# fpga-config.net
KiCad netlist of a schematic drawn in Altium Designer
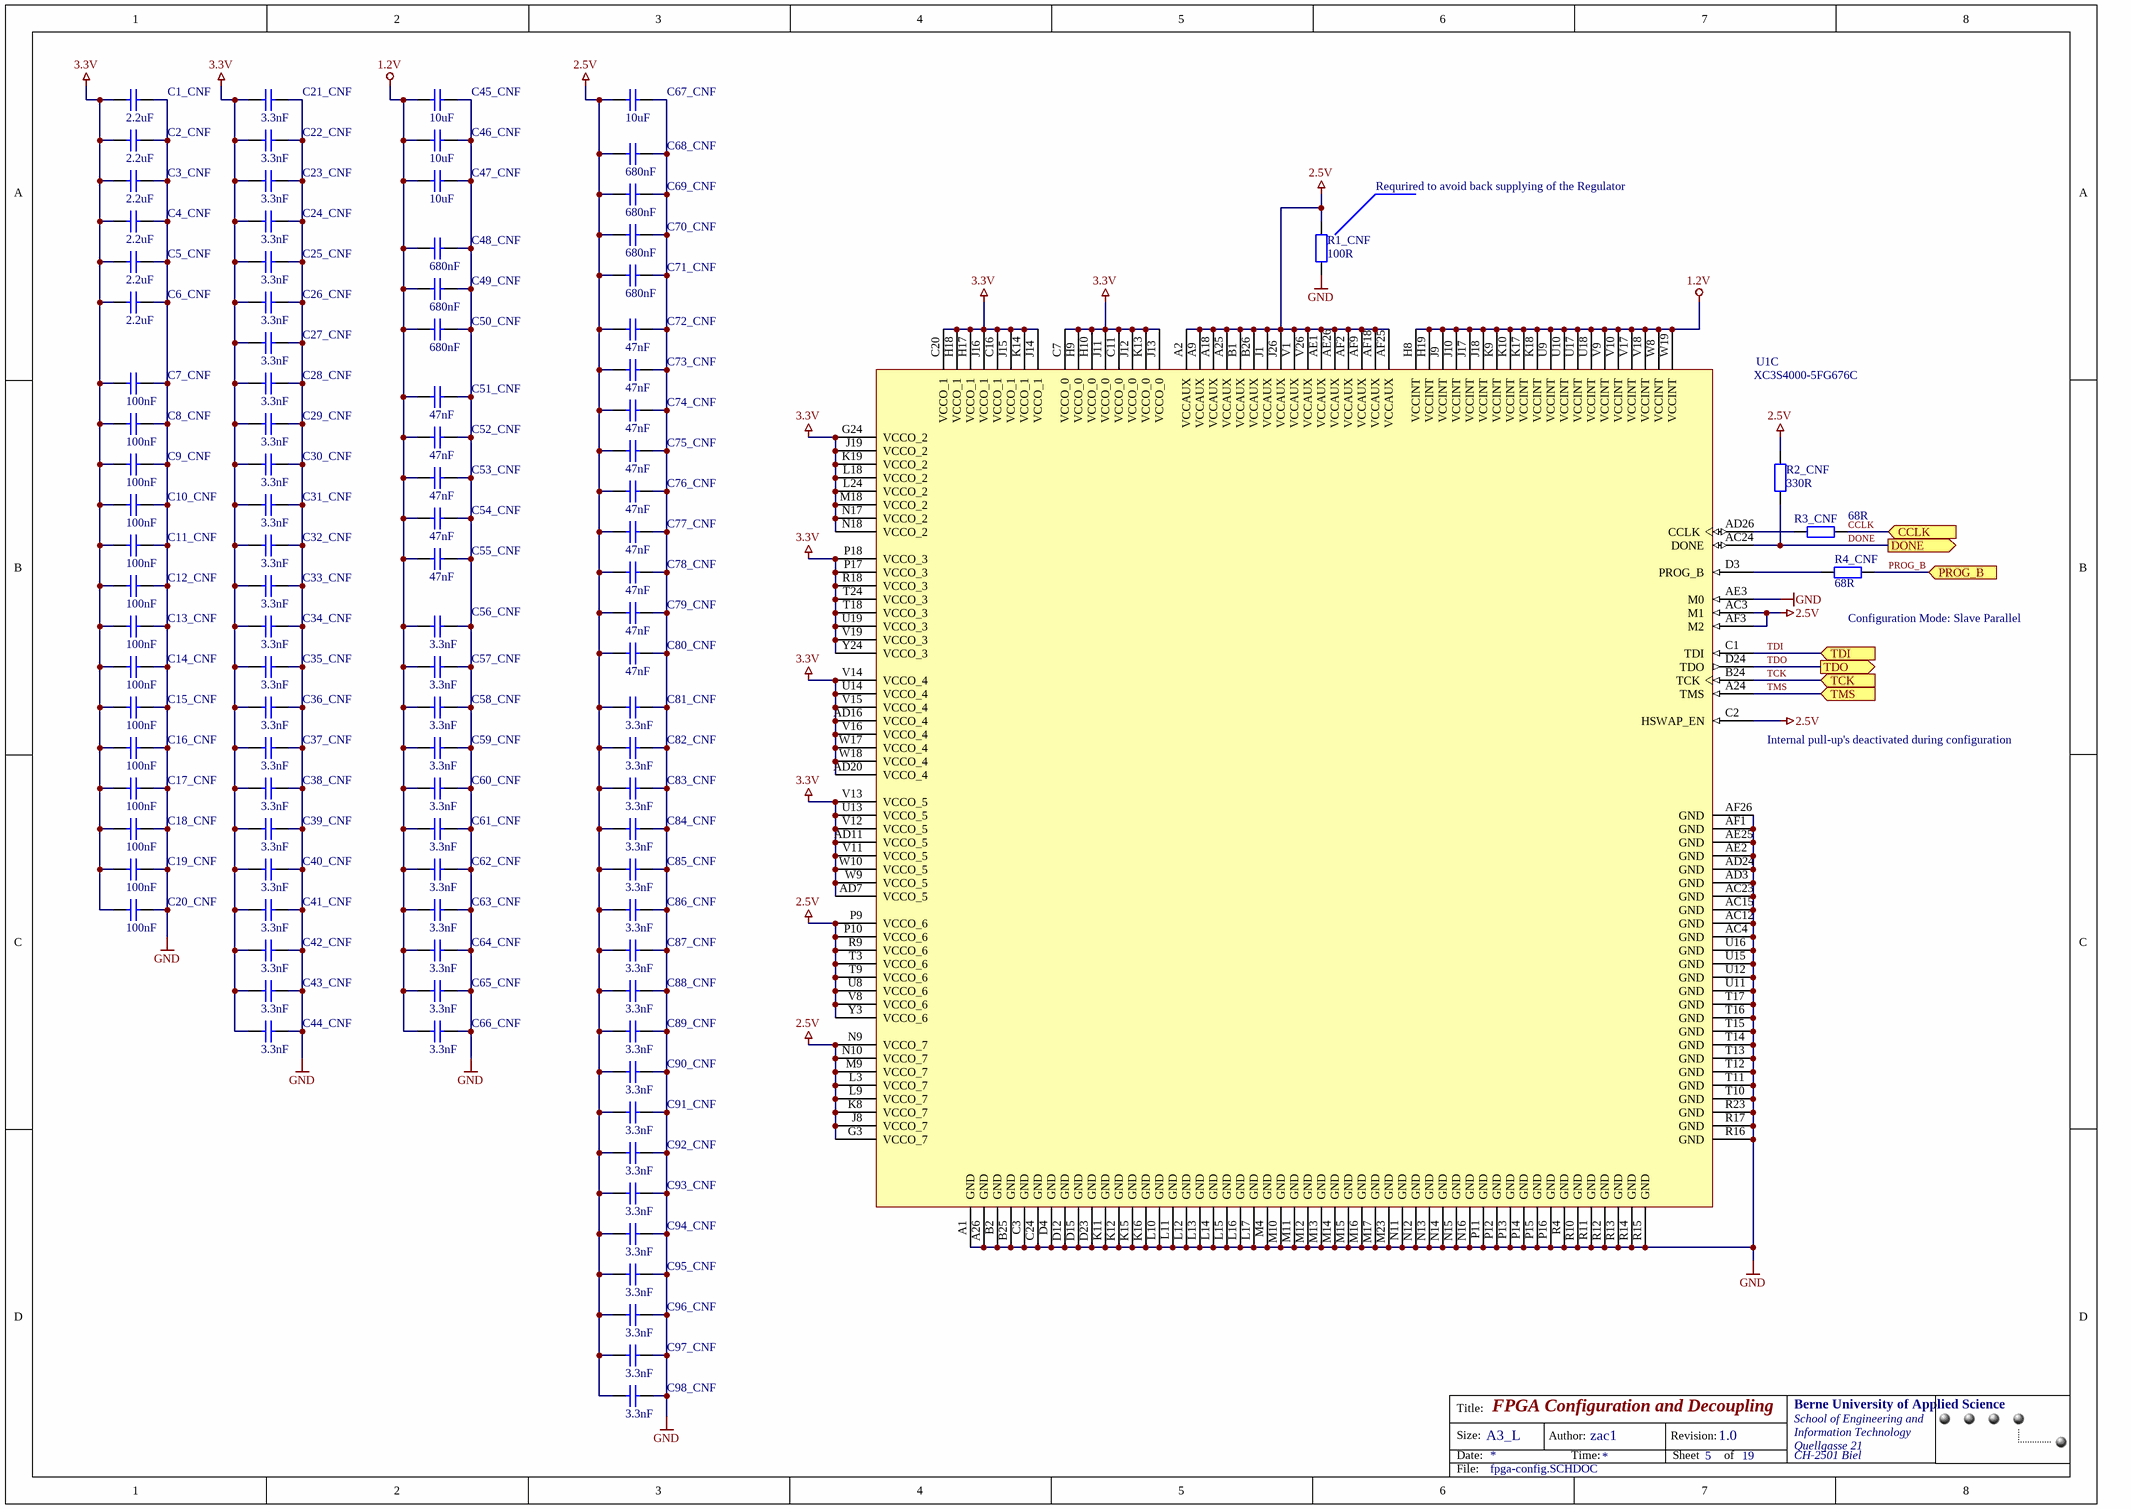
[diagram p0: fpga-config.SCHDOC]

(export (version "E")
  (design (tool "Eeschema 10.0.6"))
  (components
    (comp (ref "C1_CNF")
      (value "2.2uF")
      (footprint "0805")
      (description "Capacitor")
      (fields
        (field (name "MANUFACTURER") "Murata")
        (field (name "PART NUMBER") "GRM21BR71A225KA01L")
        (field (name "PUBLISHER") "Altium Limited")
      )
      (libsource (lib "Miscellaneous Devices") (part "Cap"))
    )
    (comp (ref "C2_CNF")
      (value "2.2uF")
      (footprint "0805")
      (description "Capacitor")
      (fields
        (field (name "MANUFACTURER") "Murata")
        (field (name "PART NUMBER") "GRM21BR71A225KA01L")
        (field (name "PUBLISHER") "Altium Limited")
      )
      (libsource (lib "Miscellaneous Devices") (part "Cap"))
    )
    (comp (ref "C3_CNF")
      (value "2.2uF")
      (footprint "0805")
      (description "Capacitor")
      (fields
        (field (name "MANUFACTURER") "Murata")
        (field (name "PART NUMBER") "GRM21BR71A225KA01L")
        (field (name "PUBLISHER") "Altium Limited")
      )
      (libsource (lib "Miscellaneous Devices") (part "Cap"))
    )
    (comp (ref "C4_CNF")
      (value "2.2uF")
      (footprint "0805")
      (description "Capacitor")
      (fields
        (field (name "MANUFACTURER") "Murata")
        (field (name "PART NUMBER") "GRM21BR71A225KA01L")
        (field (name "PUBLISHER") "Altium Limited")
      )
      (libsource (lib "Miscellaneous Devices") (part "Cap"))
    )
    (comp (ref "C5_CNF")
      (value "2.2uF")
      (footprint "0805")
      (description "Capacitor")
      (fields
        (field (name "MANUFACTURER") "Murata")
        (field (name "PART NUMBER") "GRM21BR71A225KA01L")
        (field (name "PUBLISHER") "Altium Limited")
      )
      (libsource (lib "Miscellaneous Devices") (part "Cap"))
    )
    (comp (ref "C6_CNF")
      (value "2.2uF")
      (footprint "0805")
      (description "Capacitor")
      (fields
        (field (name "MANUFACTURER") "Murata")
        (field (name "PART NUMBER") "GRM21BR71A225KA01L")
        (field (name "PUBLISHER") "Altium Limited")
      )
      (libsource (lib "Miscellaneous Devices") (part "Cap"))
    )
    (comp (ref "C7_CNF")
      (value "100nF")
      (footprint "0402")
      (description "Capacitor")
      (fields
        (field (name "MANUFACTURER") "Murata")
        (field (name "PART NUMBER") "GRM155R71C104KA88D")
        (field (name "PUBLISHER") "Altium Limited")
      )
      (libsource (lib "Miscellaneous Devices") (part "Cap"))
    )
    (comp (ref "C8_CNF")
      (value "100nF")
      (footprint "0402")
      (description "Capacitor")
      (fields
        (field (name "MANUFACTURER") "Murata")
        (field (name "PART NUMBER") "GRM155R71C104KA88D")
        (field (name "PUBLISHER") "Altium Limited")
      )
      (libsource (lib "Miscellaneous Devices") (part "Cap"))
    )
    (comp (ref "C9_CNF")
      (value "100nF")
      (footprint "0402")
      (description "Capacitor")
      (fields
        (field (name "MANUFACTURER") "Murata")
        (field (name "PART NUMBER") "GRM155R71C104KA88D")
        (field (name "PUBLISHER") "Altium Limited")
      )
      (libsource (lib "Miscellaneous Devices") (part "Cap"))
    )
    (comp (ref "C10_CNF")
      (value "100nF")
      (footprint "0402")
      (description "Capacitor")
      (fields
        (field (name "MANUFACTURER") "Murata")
        (field (name "PART NUMBER") "GRM155R71C104KA88D")
        (field (name "PUBLISHER") "Altium Limited")
      )
      (libsource (lib "Miscellaneous Devices") (part "Cap"))
    )
    (comp (ref "C11_CNF")
      (value "100nF")
      (footprint "0402")
      (description "Capacitor")
      (fields
        (field (name "MANUFACTURER") "Murata")
        (field (name "PART NUMBER") "GRM155R71C104KA88D")
        (field (name "PUBLISHER") "Altium Limited")
      )
      (libsource (lib "Miscellaneous Devices") (part "Cap"))
    )
    (comp (ref "C12_CNF")
      (value "100nF")
      (footprint "0402")
      (description "Capacitor")
      (fields
        (field (name "MANUFACTURER") "Murata")
        (field (name "PART NUMBER") "GRM155R71C104KA88D")
        (field (name "PUBLISHER") "Altium Limited")
      )
      (libsource (lib "Miscellaneous Devices") (part "Cap"))
    )
    (comp (ref "C13_CNF")
      (value "100nF")
      (footprint "0402")
      (description "Capacitor")
      (fields
        (field (name "MANUFACTURER") "Murata")
        (field (name "PART NUMBER") "GRM155R71C104KA88D")
        (field (name "PUBLISHER") "Altium Limited")
      )
      (libsource (lib "Miscellaneous Devices") (part "Cap"))
    )
    (comp (ref "C14_CNF")
      (value "100nF")
      (footprint "0402")
      (description "Capacitor")
      (fields
        (field (name "MANUFACTURER") "Murata")
        (field (name "PART NUMBER") "GRM155R71C104KA88D")
        (field (name "PUBLISHER") "Altium Limited")
      )
      (libsource (lib "Miscellaneous Devices") (part "Cap"))
    )
    (comp (ref "C15_CNF")
      (value "100nF")
      (footprint "0402")
      (description "Capacitor")
      (fields
        (field (name "MANUFACTURER") "Murata")
        (field (name "PART NUMBER") "GRM155R71C104KA88D")
        (field (name "PUBLISHER") "Altium Limited")
      )
      (libsource (lib "Miscellaneous Devices") (part "Cap"))
    )
    (comp (ref "C16_CNF")
      (value "100nF")
      (footprint "0402")
      (description "Capacitor")
      (fields
        (field (name "MANUFACTURER") "Murata")
        (field (name "PART NUMBER") "GRM155R71C104KA88D")
        (field (name "PUBLISHER") "Altium Limited")
      )
      (libsource (lib "Miscellaneous Devices") (part "Cap"))
    )
    (comp (ref "C17_CNF")
      (value "100nF")
      (footprint "0402")
      (description "Capacitor")
      (fields
        (field (name "MANUFACTURER") "Murata")
        (field (name "PART NUMBER") "GRM155R71C104KA88D")
        (field (name "PUBLISHER") "Altium Limited")
      )
      (libsource (lib "Miscellaneous Devices") (part "Cap"))
    )
    (comp (ref "C18_CNF")
      (value "100nF")
      (footprint "0402")
      (description "Capacitor")
      (fields
        (field (name "MANUFACTURER") "Murata")
        (field (name "PART NUMBER") "GRM155R71C104KA88D")
        (field (name "PUBLISHER") "Altium Limited")
      )
      (libsource (lib "Miscellaneous Devices") (part "Cap"))
    )
    (comp (ref "C19_CNF")
      (value "100nF")
      (footprint "0402")
      (description "Capacitor")
      (fields
        (field (name "MANUFACTURER") "Murata")
        (field (name "PART NUMBER") "GRM155R71C104KA88D")
        (field (name "PUBLISHER") "Altium Limited")
      )
      (libsource (lib "Miscellaneous Devices") (part "Cap"))
    )
    (comp (ref "C20_CNF")
      (value "100nF")
      (footprint "0402")
      (description "Capacitor")
      (fields
        (field (name "MANUFACTURER") "Murata")
        (field (name "PART NUMBER") "GRM155R71C104KA88D")
        (field (name "PUBLISHER") "Altium Limited")
      )
      (libsource (lib "Miscellaneous Devices") (part "Cap"))
    )
    (comp (ref "C21_CNF")
      (value "3.3nF")
      (footprint "0402")
      (description "Capacitor")
      (fields
        (field (name "MANUFACTURER") "PHYCOMP")
        (field (name "PART NUMBER") "2238 587 15629")
        (field (name "PUBLISHER") "Altium Limited")
      )
      (libsource (lib "Miscellaneous Devices") (part "Cap"))
    )
    (comp (ref "C22_CNF")
      (value "3.3nF")
      (footprint "0402")
      (description "Capacitor")
      (fields
        (field (name "MANUFACTURER") "PHYCOMP")
        (field (name "PART NUMBER") "2238 587 15629")
        (field (name "PUBLISHER") "Altium Limited")
      )
      (libsource (lib "Miscellaneous Devices") (part "Cap"))
    )
    (comp (ref "C23_CNF")
      (value "3.3nF")
      (footprint "0402")
      (description "Capacitor")
      (fields
        (field (name "MANUFACTURER") "PHYCOMP")
        (field (name "PART NUMBER") "2238 587 15629")
        (field (name "PUBLISHER") "Altium Limited")
      )
      (libsource (lib "Miscellaneous Devices") (part "Cap"))
    )
    (comp (ref "C24_CNF")
      (value "3.3nF")
      (footprint "0402")
      (description "Capacitor")
      (fields
        (field (name "MANUFACTURER") "PHYCOMP")
        (field (name "PART NUMBER") "2238 587 15629")
        (field (name "PUBLISHER") "Altium Limited")
      )
      (libsource (lib "Miscellaneous Devices") (part "Cap"))
    )
    (comp (ref "C25_CNF")
      (value "3.3nF")
      (footprint "0402")
      (description "Capacitor")
      (fields
        (field (name "MANUFACTURER") "PHYCOMP")
        (field (name "PART NUMBER") "2238 587 15629")
        (field (name "PUBLISHER") "Altium Limited")
      )
      (libsource (lib "Miscellaneous Devices") (part "Cap"))
    )
    (comp (ref "C26_CNF")
      (value "3.3nF")
      (footprint "0402")
      (description "Capacitor")
      (fields
        (field (name "MANUFACTURER") "PHYCOMP")
        (field (name "PART NUMBER") "2238 587 15629")
        (field (name "PUBLISHER") "Altium Limited")
      )
      (libsource (lib "Miscellaneous Devices") (part "Cap"))
    )
    (comp (ref "C27_CNF")
      (value "3.3nF")
      (footprint "0402")
      (description "Capacitor")
      (fields
        (field (name "MANUFACTURER") "PHYCOMP")
        (field (name "PART NUMBER") "2238 587 15629")
        (field (name "PUBLISHER") "Altium Limited")
      )
      (libsource (lib "Miscellaneous Devices") (part "Cap"))
    )
    (comp (ref "C28_CNF")
      (value "3.3nF")
      (footprint "0402")
      (description "Capacitor")
      (fields
        (field (name "MANUFACTURER") "PHYCOMP")
        (field (name "PART NUMBER") "2238 587 15629")
        (field (name "PUBLISHER") "Altium Limited")
      )
      (libsource (lib "Miscellaneous Devices") (part "Cap"))
    )
    (comp (ref "C29_CNF")
      (value "3.3nF")
      (footprint "0402")
      (description "Capacitor")
      (fields
        (field (name "MANUFACTURER") "PHYCOMP")
        (field (name "PART NUMBER") "2238 587 15629")
        (field (name "PUBLISHER") "Altium Limited")
      )
      (libsource (lib "Miscellaneous Devices") (part "Cap"))
    )
    (comp (ref "C30_CNF")
      (value "3.3nF")
      (footprint "0402")
      (description "Capacitor")
      (fields
        (field (name "MANUFACTURER") "PHYCOMP")
        (field (name "PART NUMBER") "2238 587 15629")
        (field (name "PUBLISHER") "Altium Limited")
      )
      (libsource (lib "Miscellaneous Devices") (part "Cap"))
    )
    (comp (ref "C31_CNF")
      (value "3.3nF")
      (footprint "0402")
      (description "Capacitor")
      (fields
        (field (name "MANUFACTURER") "PHYCOMP")
        (field (name "PART NUMBER") "2238 587 15629")
        (field (name "PUBLISHER") "Altium Limited")
      )
      (libsource (lib "Miscellaneous Devices") (part "Cap"))
    )
    (comp (ref "C32_CNF")
      (value "3.3nF")
      (footprint "0402")
      (description "Capacitor")
      (fields
        (field (name "MANUFACTURER") "PHYCOMP")
        (field (name "PART NUMBER") "2238 587 15629")
        (field (name "PUBLISHER") "Altium Limited")
      )
      (libsource (lib "Miscellaneous Devices") (part "Cap"))
    )
    (comp (ref "C33_CNF")
      (value "3.3nF")
      (footprint "0402")
      (description "Capacitor")
      (fields
        (field (name "MANUFACTURER") "PHYCOMP")
        (field (name "PART NUMBER") "2238 587 15629")
        (field (name "PUBLISHER") "Altium Limited")
      )
      (libsource (lib "Miscellaneous Devices") (part "Cap"))
    )
    (comp (ref "C34_CNF")
      (value "3.3nF")
      (footprint "0402")
      (description "Capacitor")
      (fields
        (field (name "MANUFACTURER") "PHYCOMP")
        (field (name "PART NUMBER") "2238 587 15629")
        (field (name "PUBLISHER") "Altium Limited")
      )
      (libsource (lib "Miscellaneous Devices") (part "Cap"))
    )
    (comp (ref "C35_CNF")
      (value "3.3nF")
      (footprint "0402")
      (description "Capacitor")
      (fields
        (field (name "MANUFACTURER") "PHYCOMP")
        (field (name "PART NUMBER") "2238 587 15629")
        (field (name "PUBLISHER") "Altium Limited")
      )
      (libsource (lib "Miscellaneous Devices") (part "Cap"))
    )
    (comp (ref "C36_CNF")
      (value "3.3nF")
      (footprint "0402")
      (description "Capacitor")
      (fields
        (field (name "MANUFACTURER") "PHYCOMP")
        (field (name "PART NUMBER") "2238 587 15629")
        (field (name "PUBLISHER") "Altium Limited")
      )
      (libsource (lib "Miscellaneous Devices") (part "Cap"))
    )
    (comp (ref "C37_CNF")
      (value "3.3nF")
      (footprint "0402")
      (description "Capacitor")
      (fields
        (field (name "MANUFACTURER") "PHYCOMP")
        (field (name "PART NUMBER") "2238 587 15629")
        (field (name "PUBLISHER") "Altium Limited")
      )
      (libsource (lib "Miscellaneous Devices") (part "Cap"))
    )
    (comp (ref "C38_CNF")
      (value "3.3nF")
      (footprint "0402")
      (description "Capacitor")
      (fields
        (field (name "MANUFACTURER") "PHYCOMP")
        (field (name "PART NUMBER") "2238 587 15629")
        (field (name "PUBLISHER") "Altium Limited")
      )
      (libsource (lib "Miscellaneous Devices") (part "Cap"))
    )
    (comp (ref "C39_CNF")
      (value "3.3nF")
      (footprint "0402")
      (description "Capacitor")
      (fields
        (field (name "MANUFACTURER") "PHYCOMP")
        (field (name "PART NUMBER") "2238 587 15629")
        (field (name "PUBLISHER") "Altium Limited")
      )
      (libsource (lib "Miscellaneous Devices") (part "Cap"))
    )
    (comp (ref "C40_CNF")
      (value "3.3nF")
      (footprint "0402")
      (description "Capacitor")
      (fields
        (field (name "MANUFACTURER") "PHYCOMP")
        (field (name "PART NUMBER") "2238 587 15629")
        (field (name "PUBLISHER") "Altium Limited")
      )
      (libsource (lib "Miscellaneous Devices") (part "Cap"))
    )
    (comp (ref "C41_CNF")
      (value "3.3nF")
      (footprint "0402")
      (description "Capacitor")
      (fields
        (field (name "MANUFACTURER") "PHYCOMP")
        (field (name "PART NUMBER") "2238 587 15629")
        (field (name "PUBLISHER") "Altium Limited")
      )
      (libsource (lib "Miscellaneous Devices") (part "Cap"))
    )
    (comp (ref "C42_CNF")
      (value "3.3nF")
      (footprint "0402")
      (description "Capacitor")
      (fields
        (field (name "MANUFACTURER") "PHYCOMP")
        (field (name "PART NUMBER") "2238 587 15629")
        (field (name "PUBLISHER") "Altium Limited")
      )
      (libsource (lib "Miscellaneous Devices") (part "Cap"))
    )
    (comp (ref "C43_CNF")
      (value "3.3nF")
      (footprint "0402")
      (description "Capacitor")
      (fields
        (field (name "MANUFACTURER") "PHYCOMP")
        (field (name "PART NUMBER") "2238 587 15629")
        (field (name "PUBLISHER") "Altium Limited")
      )
      (libsource (lib "Miscellaneous Devices") (part "Cap"))
    )
    (comp (ref "C44_CNF")
      (value "3.3nF")
      (footprint "0402")
      (description "Capacitor")
      (fields
        (field (name "MANUFACTURER") "PHYCOMP")
        (field (name "PART NUMBER") "2238 587 15629")
        (field (name "PUBLISHER") "Altium Limited")
      )
      (libsource (lib "Miscellaneous Devices") (part "Cap"))
    )
    (comp (ref "C45_CNF")
      (value "10uF")
      (footprint "1206")
      (description "Capacitor")
      (fields
        (field (name "MANUFACTURER") "Murata")
        (field (name "PART NUMBER") "GRM31CR70J106KA01L")
        (field (name "PUBLISHER") "Altium Limited")
      )
      (libsource (lib "Miscellaneous Devices") (part "Cap"))
    )
    (comp (ref "C46_CNF")
      (value "10uF")
      (footprint "1206")
      (description "Capacitor")
      (fields
        (field (name "MANUFACTURER") "Murata")
        (field (name "PART NUMBER") "GRM31CR70J106KA01L")
        (field (name "PUBLISHER") "Altium Limited")
      )
      (libsource (lib "Miscellaneous Devices") (part "Cap"))
    )
    (comp (ref "C47_CNF")
      (value "10uF")
      (footprint "1206")
      (description "Capacitor")
      (fields
        (field (name "MANUFACTURER") "Murata")
        (field (name "PART NUMBER") "GRM31CR70J106KA01L")
        (field (name "PUBLISHER") "Altium Limited")
      )
      (libsource (lib "Miscellaneous Devices") (part "Cap"))
    )
    (comp (ref "C48_CNF")
      (value "680nF")
      (footprint "0805")
      (description "Capacitor")
      (fields
        (field (name "MANUFACTURER") "PHYCOMP")
        (field (name "PART NUMBER") "2238 240 15661")
        (field (name "PUBLISHER") "Altium Limited")
      )
      (libsource (lib "Miscellaneous Devices") (part "Cap"))
    )
    (comp (ref "C49_CNF")
      (value "680nF")
      (footprint "0805")
      (description "Capacitor")
      (fields
        (field (name "MANUFACTURER") "PHYCOMP")
        (field (name "PART NUMBER") "2238 240 15661")
        (field (name "PUBLISHER") "Altium Limited")
      )
      (libsource (lib "Miscellaneous Devices") (part "Cap"))
    )
    (comp (ref "C50_CNF")
      (value "680nF")
      (footprint "0805")
      (description "Capacitor")
      (fields
        (field (name "MANUFACTURER") "PHYCOMP")
        (field (name "PART NUMBER") "2238 240 15661")
        (field (name "PUBLISHER") "Altium Limited")
      )
      (libsource (lib "Miscellaneous Devices") (part "Cap"))
    )
    (comp (ref "C51_CNF")
      (value "47nF")
      (footprint "0402")
      (description "Capacitor")
      (fields
        (field (name "MANUFACTURER") "PHYCOMP")
        (field (name "PART NUMBER") "2238 787 19845")
        (field (name "PUBLISHER") "Altium Limited")
      )
      (libsource (lib "Miscellaneous Devices") (part "Cap"))
    )
    (comp (ref "C52_CNF")
      (value "47nF")
      (footprint "0402")
      (description "Capacitor")
      (fields
        (field (name "MANUFACTURER") "PHYCOMP")
        (field (name "PART NUMBER") "2238 787 19845")
        (field (name "PUBLISHER") "Altium Limited")
      )
      (libsource (lib "Miscellaneous Devices") (part "Cap"))
    )
    (comp (ref "C53_CNF")
      (value "47nF")
      (footprint "0402")
      (description "Capacitor")
      (fields
        (field (name "MANUFACTURER") "PHYCOMP")
        (field (name "PART NUMBER") "2238 787 19845")
        (field (name "PUBLISHER") "Altium Limited")
      )
      (libsource (lib "Miscellaneous Devices") (part "Cap"))
    )
    (comp (ref "C54_CNF")
      (value "47nF")
      (footprint "0402")
      (description "Capacitor")
      (fields
        (field (name "MANUFACTURER") "PHYCOMP")
        (field (name "PART NUMBER") "2238 787 19845")
        (field (name "PUBLISHER") "Altium Limited")
      )
      (libsource (lib "Miscellaneous Devices") (part "Cap"))
    )
    (comp (ref "C55_CNF")
      (value "47nF")
      (footprint "0402")
      (description "Capacitor")
      (fields
        (field (name "MANUFACTURER") "PHYCOMP")
        (field (name "PART NUMBER") "2238 787 19845")
        (field (name "PUBLISHER") "Altium Limited")
      )
      (libsource (lib "Miscellaneous Devices") (part "Cap"))
    )
    (comp (ref "C56_CNF")
      (value "3.3nF")
      (footprint "0402")
      (description "Capacitor")
      (fields
        (field (name "MANUFACTURER") "PHYCOMP")
        (field (name "PART NUMBER") "2238 587 15629")
        (field (name "PUBLISHER") "Altium Limited")
      )
      (libsource (lib "Miscellaneous Devices") (part "Cap"))
    )
    (comp (ref "C57_CNF")
      (value "3.3nF")
      (footprint "0402")
      (description "Capacitor")
      (fields
        (field (name "MANUFACTURER") "PHYCOMP")
        (field (name "PART NUMBER") "2238 587 15629")
        (field (name "PUBLISHER") "Altium Limited")
      )
      (libsource (lib "Miscellaneous Devices") (part "Cap"))
    )
    (comp (ref "C58_CNF")
      (value "3.3nF")
      (footprint "0402")
      (description "Capacitor")
      (fields
        (field (name "MANUFACTURER") "PHYCOMP")
        (field (name "PART NUMBER") "2238 587 15629")
        (field (name "PUBLISHER") "Altium Limited")
      )
      (libsource (lib "Miscellaneous Devices") (part "Cap"))
    )
    (comp (ref "C59_CNF")
      (value "3.3nF")
      (footprint "0402")
      (description "Capacitor")
      (fields
        (field (name "MANUFACTURER") "PHYCOMP")
        (field (name "PART NUMBER") "2238 587 15629")
        (field (name "PUBLISHER") "Altium Limited")
      )
      (libsource (lib "Miscellaneous Devices") (part "Cap"))
    )
    (comp (ref "C60_CNF")
      (value "3.3nF")
      (footprint "0402")
      (description "Capacitor")
      (fields
        (field (name "MANUFACTURER") "PHYCOMP")
        (field (name "PART NUMBER") "2238 587 15629")
        (field (name "PUBLISHER") "Altium Limited")
      )
      (libsource (lib "Miscellaneous Devices") (part "Cap"))
    )
    (comp (ref "C61_CNF")
      (value "3.3nF")
      (footprint "0402")
      (description "Capacitor")
      (fields
        (field (name "MANUFACTURER") "PHYCOMP")
        (field (name "PART NUMBER") "2238 587 15629")
        (field (name "PUBLISHER") "Altium Limited")
      )
      (libsource (lib "Miscellaneous Devices") (part "Cap"))
    )
    (comp (ref "C62_CNF")
      (value "3.3nF")
      (footprint "0402")
      (description "Capacitor")
      (fields
        (field (name "MANUFACTURER") "PHYCOMP")
        (field (name "PART NUMBER") "2238 587 15629")
        (field (name "PUBLISHER") "Altium Limited")
      )
      (libsource (lib "Miscellaneous Devices") (part "Cap"))
    )
    (comp (ref "C63_CNF")
      (value "3.3nF")
      (footprint "0402")
      (description "Capacitor")
      (fields
        (field (name "MANUFACTURER") "PHYCOMP")
        (field (name "PART NUMBER") "2238 587 15629")
        (field (name "PUBLISHER") "Altium Limited")
      )
      (libsource (lib "Miscellaneous Devices") (part "Cap"))
    )
    (comp (ref "C64_CNF")
      (value "3.3nF")
      (footprint "0402")
      (description "Capacitor")
      (fields
        (field (name "MANUFACTURER") "PHYCOMP")
        (field (name "PART NUMBER") "2238 587 15629")
        (field (name "PUBLISHER") "Altium Limited")
      )
      (libsource (lib "Miscellaneous Devices") (part "Cap"))
    )
    (comp (ref "C65_CNF")
      (value "3.3nF")
      (footprint "0402")
      (description "Capacitor")
      (fields
        (field (name "MANUFACTURER") "PHYCOMP")
        (field (name "PART NUMBER") "2238 587 15629")
        (field (name "PUBLISHER") "Altium Limited")
      )
      (libsource (lib "Miscellaneous Devices") (part "Cap"))
    )
    (comp (ref "C66_CNF")
      (value "3.3nF")
      (footprint "0402")
      (description "Capacitor")
      (fields
        (field (name "MANUFACTURER") "PHYCOMP")
        (field (name "PART NUMBER") "2238 587 15629")
        (field (name "PUBLISHER") "Altium Limited")
      )
      (libsource (lib "Miscellaneous Devices") (part "Cap"))
    )
    (comp (ref "C67_CNF")
      (value "10uF")
      (footprint "1206")
      (description "Capacitor")
      (fields
        (field (name "MANUFACTURER") "Murata")
        (field (name "PART NUMBER") "GRM31CR70J106KA01L")
        (field (name "PUBLISHER") "Altium Limited")
      )
      (libsource (lib "Miscellaneous Devices") (part "Cap"))
    )
    (comp (ref "C68_CNF")
      (value "680nF")
      (footprint "0805")
      (description "Capacitor")
      (fields
        (field (name "MANUFACTURER") "PHYCOMP")
        (field (name "PART NUMBER") "2238 240 15661")
        (field (name "PUBLISHER") "Altium Limited")
      )
      (libsource (lib "Miscellaneous Devices") (part "Cap"))
    )
    (comp (ref "C69_CNF")
      (value "680nF")
      (footprint "0805")
      (description "Capacitor")
      (fields
        (field (name "MANUFACTURER") "PHYCOMP")
        (field (name "PART NUMBER") "2238 240 15661")
        (field (name "PUBLISHER") "Altium Limited")
      )
      (libsource (lib "Miscellaneous Devices") (part "Cap"))
    )
    (comp (ref "C70_CNF")
      (value "680nF")
      (footprint "0805")
      (description "Capacitor")
      (fields
        (field (name "MANUFACTURER") "PHYCOMP")
        (field (name "PART NUMBER") "2238 240 15661")
        (field (name "PUBLISHER") "Altium Limited")
      )
      (libsource (lib "Miscellaneous Devices") (part "Cap"))
    )
    (comp (ref "C71_CNF")
      (value "680nF")
      (footprint "0805")
      (description "Capacitor")
      (fields
        (field (name "MANUFACTURER") "PHYCOMP")
        (field (name "PART NUMBER") "2238 240 15661")
        (field (name "PUBLISHER") "Altium Limited")
      )
      (libsource (lib "Miscellaneous Devices") (part "Cap"))
    )
    (comp (ref "C72_CNF")
      (value "47nF")
      (footprint "0402")
      (description "Capacitor")
      (fields
        (field (name "MANUFACTURER") "PHYCOMP")
        (field (name "PART NUMBER") "2238 787 19845")
        (field (name "PUBLISHER") "Altium Limited")
      )
      (libsource (lib "Miscellaneous Devices") (part "Cap"))
    )
    (comp (ref "C73_CNF")
      (value "47nF")
      (footprint "0402")
      (description "Capacitor")
      (fields
        (field (name "MANUFACTURER") "PHYCOMP")
        (field (name "PART NUMBER") "2238 787 19845")
        (field (name "PUBLISHER") "Altium Limited")
      )
      (libsource (lib "Miscellaneous Devices") (part "Cap"))
    )
    (comp (ref "C74_CNF")
      (value "47nF")
      (footprint "0402")
      (description "Capacitor")
      (fields
        (field (name "MANUFACTURER") "PHYCOMP")
        (field (name "PART NUMBER") "2238 787 19845")
        (field (name "PUBLISHER") "Altium Limited")
      )
      (libsource (lib "Miscellaneous Devices") (part "Cap"))
    )
    (comp (ref "C75_CNF")
      (value "47nF")
      (footprint "0402")
      (description "Capacitor")
      (fields
        (field (name "MANUFACTURER") "PHYCOMP")
        (field (name "PART NUMBER") "2238 787 19845")
        (field (name "PUBLISHER") "Altium Limited")
      )
      (libsource (lib "Miscellaneous Devices") (part "Cap"))
    )
    (comp (ref "C76_CNF")
      (value "47nF")
      (footprint "0402")
      (description "Capacitor")
      (fields
        (field (name "MANUFACTURER") "PHYCOMP")
        (field (name "PART NUMBER") "2238 787 19845")
        (field (name "PUBLISHER") "Altium Limited")
      )
      (libsource (lib "Miscellaneous Devices") (part "Cap"))
    )
    (comp (ref "C77_CNF")
      (value "47nF")
      (footprint "0402")
      (description "Capacitor")
      (fields
        (field (name "MANUFACTURER") "PHYCOMP")
        (field (name "PART NUMBER") "2238 787 19845")
        (field (name "PUBLISHER") "Altium Limited")
      )
      (libsource (lib "Miscellaneous Devices") (part "Cap"))
    )
    (comp (ref "C78_CNF")
      (value "47nF")
      (footprint "0402")
      (description "Capacitor")
      (fields
        (field (name "MANUFACTURER") "PHYCOMP")
        (field (name "PART NUMBER") "2238 787 19845")
        (field (name "PUBLISHER") "Altium Limited")
      )
      (libsource (lib "Miscellaneous Devices") (part "Cap"))
    )
    (comp (ref "C79_CNF")
      (value "47nF")
      (footprint "0402")
      (description "Capacitor")
      (fields
        (field (name "MANUFACTURER") "PHYCOMP")
        (field (name "PART NUMBER") "2238 787 19845")
        (field (name "PUBLISHER") "Altium Limited")
      )
      (libsource (lib "Miscellaneous Devices") (part "Cap"))
    )
    (comp (ref "C80_CNF")
      (value "47nF")
      (footprint "0402")
      (description "Capacitor")
      (fields
        (field (name "MANUFACTURER") "PHYCOMP")
        (field (name "PART NUMBER") "2238 787 19845")
        (field (name "PUBLISHER") "Altium Limited")
      )
      (libsource (lib "Miscellaneous Devices") (part "Cap"))
    )
    (comp (ref "C81_CNF")
      (value "3.3nF")
      (footprint "0402")
      (description "Capacitor")
      (fields
        (field (name "MANUFACTURER") "PHYCOMP")
        (field (name "PART NUMBER") "2238 587 15629")
        (field (name "PUBLISHER") "Altium Limited")
      )
      (libsource (lib "Miscellaneous Devices") (part "Cap"))
    )
    (comp (ref "C82_CNF")
      (value "3.3nF")
      (footprint "0402")
      (description "Capacitor")
      (fields
        (field (name "MANUFACTURER") "PHYCOMP")
        (field (name "PART NUMBER") "2238 587 15629")
        (field (name "PUBLISHER") "Altium Limited")
      )
      (libsource (lib "Miscellaneous Devices") (part "Cap"))
    )
    (comp (ref "C83_CNF")
      (value "3.3nF")
      (footprint "0402")
      (description "Capacitor")
      (fields
        (field (name "MANUFACTURER") "PHYCOMP")
        (field (name "PART NUMBER") "2238 587 15629")
        (field (name "PUBLISHER") "Altium Limited")
      )
      (libsource (lib "Miscellaneous Devices") (part "Cap"))
    )
    (comp (ref "C84_CNF")
      (value "3.3nF")
      (footprint "0402")
      (description "Capacitor")
      (fields
        (field (name "MANUFACTURER") "PHYCOMP")
        (field (name "PART NUMBER") "2238 587 15629")
        (field (name "PUBLISHER") "Altium Limited")
      )
      (libsource (lib "Miscellaneous Devices") (part "Cap"))
    )
    (comp (ref "C85_CNF")
      (value "3.3nF")
      (footprint "0402")
      (description "Capacitor")
      (fields
        (field (name "MANUFACTURER") "PHYCOMP")
        (field (name "PART NUMBER") "2238 587 15629")
        (field (name "PUBLISHER") "Altium Limited")
      )
      (libsource (lib "Miscellaneous Devices") (part "Cap"))
    )
    (comp (ref "C86_CNF")
      (value "3.3nF")
      (footprint "0402")
      (description "Capacitor")
      (fields
        (field (name "MANUFACTURER") "PHYCOMP")
        (field (name "PART NUMBER") "2238 587 15629")
        (field (name "PUBLISHER") "Altium Limited")
      )
      (libsource (lib "Miscellaneous Devices") (part "Cap"))
    )
    (comp (ref "C87_CNF")
      (value "3.3nF")
      (footprint "0402")
      (description "Capacitor")
      (fields
        (field (name "MANUFACTURER") "PHYCOMP")
        (field (name "PART NUMBER") "2238 587 15629")
        (field (name "PUBLISHER") "Altium Limited")
      )
      (libsource (lib "Miscellaneous Devices") (part "Cap"))
    )
    (comp (ref "C88_CNF")
      (value "3.3nF")
      (footprint "0402")
      (description "Capacitor")
      (fields
        (field (name "MANUFACTURER") "PHYCOMP")
        (field (name "PART NUMBER") "2238 587 15629")
        (field (name "PUBLISHER") "Altium Limited")
      )
      (libsource (lib "Miscellaneous Devices") (part "Cap"))
    )
    (comp (ref "C89_CNF")
      (value "3.3nF")
      (footprint "0402")
      (description "Capacitor")
      (fields
        (field (name "MANUFACTURER") "PHYCOMP")
        (field (name "PART NUMBER") "2238 587 15629")
        (field (name "PUBLISHER") "Altium Limited")
      )
      (libsource (lib "Miscellaneous Devices") (part "Cap"))
    )
    (comp (ref "C90_CNF")
      (value "3.3nF")
      (footprint "0402")
      (description "Capacitor")
      (fields
        (field (name "MANUFACTURER") "PHYCOMP")
        (field (name "PART NUMBER") "2238 587 15629")
        (field (name "PUBLISHER") "Altium Limited")
      )
      (libsource (lib "Miscellaneous Devices") (part "Cap"))
    )
    (comp (ref "C91_CNF")
      (value "3.3nF")
      (footprint "0402")
      (description "Capacitor")
      (fields
        (field (name "MANUFACTURER") "PHYCOMP")
        (field (name "PART NUMBER") "2238 587 15629")
        (field (name "PUBLISHER") "Altium Limited")
      )
      (libsource (lib "Miscellaneous Devices") (part "Cap"))
    )
    (comp (ref "C92_CNF")
      (value "3.3nF")
      (footprint "0402")
      (description "Capacitor")
      (fields
        (field (name "MANUFACTURER") "PHYCOMP")
        (field (name "PART NUMBER") "2238 587 15629")
        (field (name "PUBLISHER") "Altium Limited")
      )
      (libsource (lib "Miscellaneous Devices") (part "Cap"))
    )
    (comp (ref "C93_CNF")
      (value "3.3nF")
      (footprint "0402")
      (description "Capacitor")
      (fields
        (field (name "MANUFACTURER") "PHYCOMP")
        (field (name "PART NUMBER") "2238 587 15629")
        (field (name "PUBLISHER") "Altium Limited")
      )
      (libsource (lib "Miscellaneous Devices") (part "Cap"))
    )
    (comp (ref "C94_CNF")
      (value "3.3nF")
      (footprint "0402")
      (description "Capacitor")
      (fields
        (field (name "MANUFACTURER") "PHYCOMP")
        (field (name "PART NUMBER") "2238 587 15629")
        (field (name "PUBLISHER") "Altium Limited")
      )
      (libsource (lib "Miscellaneous Devices") (part "Cap"))
    )
    (comp (ref "C95_CNF")
      (value "3.3nF")
      (footprint "0402")
      (description "Capacitor")
      (fields
        (field (name "MANUFACTURER") "PHYCOMP")
        (field (name "PART NUMBER") "2238 587 15629")
        (field (name "PUBLISHER") "Altium Limited")
      )
      (libsource (lib "Miscellaneous Devices") (part "Cap"))
    )
    (comp (ref "C96_CNF")
      (value "3.3nF")
      (footprint "0402")
      (description "Capacitor")
      (fields
        (field (name "MANUFACTURER") "PHYCOMP")
        (field (name "PART NUMBER") "2238 587 15629")
        (field (name "PUBLISHER") "Altium Limited")
      )
      (libsource (lib "Miscellaneous Devices") (part "Cap"))
    )
    (comp (ref "C97_CNF")
      (value "3.3nF")
      (footprint "0402")
      (description "Capacitor")
      (fields
        (field (name "MANUFACTURER") "PHYCOMP")
        (field (name "PART NUMBER") "2238 587 15629")
        (field (name "PUBLISHER") "Altium Limited")
      )
      (libsource (lib "Miscellaneous Devices") (part "Cap"))
    )
    (comp (ref "C98_CNF")
      (value "3.3nF")
      (footprint "0402")
      (description "Capacitor")
      (fields
        (field (name "MANUFACTURER") "PHYCOMP")
        (field (name "PART NUMBER") "2238 587 15629")
        (field (name "PUBLISHER") "Altium Limited")
      )
      (libsource (lib "Miscellaneous Devices") (part "Cap"))
    )
    (comp (ref "R1_CNF")
      (value "100R")
      (footprint "0402")
      (description "Resistor")
      (fields
        (field (name "MANUFACTURER") "PHYCOMP")
        (field (name "PART NUMBER") "232270671001")
        (field (name "PUBLISHER") "Altium Limited")
      )
      (libsource (lib "") (part "Res2_1"))
    )
    (comp (ref "R2_CNF")
      (value "330R")
      (footprint "0402")
      (description "Resistor")
      (fields
        (field (name "MANUFACTURER") "PHYCOMP")
        (field (name "PART NUMBER") "232270673301")
        (field (name "PUBLISHER") "Altium Limited")
      )
      (libsource (lib "") (part "Res2_1"))
    )
    (comp (ref "R3_CNF")
      (value "68R")
      (footprint "0402")
      (description "Resistor")
      (fields
        (field (name "MANUFACTURER") "PHYCOMP")
        (field (name "PART NUMBER") "232270676809")
        (field (name "PUBLISHER") "Altium Limited")
      )
      (libsource (lib "Miscellaneous Devices") (part "Res2"))
    )
    (comp (ref "R4_CNF")
      (value "68R")
      (footprint "0402")
      (description "Resistor")
      (fields
        (field (name "MANUFACTURER") "PHYCOMP")
        (field (name "PART NUMBER") "232270676809")
        (field (name "PUBLISHER") "Altium Limited")
      )
      (libsource (lib "Miscellaneous Devices") (part "Res2"))
    )
    (comp (ref "U1")
      (value "XC3S4000-5FG676C")
      (footprint "FG676")
      (description "Spartan-3 1.2V FPGA, 487 User I/Os, 676-ball FBGA, High Performance, Commercial Grade")
      (fields (field (name "MANUFACTURER") "Xilinx") (field (name "PUBLISHER") "Altium Limited"))
      (libsource (lib "gecko3-user") (part "XC3S1500-5FG676C"))
    )
  )
  (nets
    (net (code "1") (name "/CCLK") (class "Default")
      (node (ref "R3_CNF") (pin "1") (pinfunction "1_1") (pintype "passive"))
    )
    (net (code "2") (name "/DONE") (class "Default")
      (node (ref "R2_CNF") (pin "2") (pinfunction "2_2") (pintype "passive"))
      (node (ref "U1") (pin "AC24") (pinfunction "DONE_AC24") (pintype "bidirectional"))
    )
    (net (code "3") (name "/PROG_B") (class "Default")
      (node (ref "R4_CNF") (pin "1") (pinfunction "1_1") (pintype "passive"))
    )
    (net (code "4") (name "/TCK") (class "Default")
      (node (ref "U1") (pin "B24") (pinfunction "TCK_B24") (pintype "input"))
    )
    (net (code "5") (name "/TDI") (class "Default")
      (node (ref "U1") (pin "C1") (pinfunction "TDI_C1") (pintype "input"))
    )
    (net (code "6") (name "/TDO") (class "Default")
      (node (ref "U1") (pin "D24") (pinfunction "TDO_D24") (pintype "output"))
    )
    (net (code "7") (name "/TMS") (class "Default")
      (node (ref "U1") (pin "A24") (pinfunction "TMS_A24") (pintype "input"))
    )
    (net (code "8") (name "1.2V") (class "Default")
      (node (ref "C45_CNF") (pin "2") (pinfunction "2_2") (pintype "passive"))
      (node (ref "C46_CNF") (pin "2") (pinfunction "2_2") (pintype "passive"))
      (node (ref "C47_CNF") (pin "2") (pinfunction "2_2") (pintype "passive"))
      (node (ref "C48_CNF") (pin "2") (pinfunction "2_2") (pintype "passive"))
      (node (ref "C49_CNF") (pin "2") (pinfunction "2_2") (pintype "passive"))
      (node (ref "C50_CNF") (pin "2") (pinfunction "2_2") (pintype "passive"))
      (node (ref "C51_CNF") (pin "2") (pinfunction "2_2") (pintype "passive"))
      (node (ref "C52_CNF") (pin "2") (pinfunction "2_2") (pintype "passive"))
      (node (ref "C53_CNF") (pin "2") (pinfunction "2_2") (pintype "passive"))
      (node (ref "C54_CNF") (pin "2") (pinfunction "2_2") (pintype "passive"))
      (node (ref "C55_CNF") (pin "2") (pinfunction "2_2") (pintype "passive"))
      (node (ref "C56_CNF") (pin "2") (pinfunction "2_2") (pintype "passive"))
      (node (ref "C57_CNF") (pin "2") (pinfunction "2_2") (pintype "passive"))
      (node (ref "C58_CNF") (pin "2") (pinfunction "2_2") (pintype "passive"))
      (node (ref "C59_CNF") (pin "2") (pinfunction "2_2") (pintype "passive"))
      (node (ref "C60_CNF") (pin "2") (pinfunction "2_2") (pintype "passive"))
      (node (ref "C61_CNF") (pin "2") (pinfunction "2_2") (pintype "passive"))
      (node (ref "C62_CNF") (pin "2") (pinfunction "2_2") (pintype "passive"))
      (node (ref "C63_CNF") (pin "2") (pinfunction "2_2") (pintype "passive"))
      (node (ref "C64_CNF") (pin "2") (pinfunction "2_2") (pintype "passive"))
      (node (ref "C65_CNF") (pin "2") (pinfunction "2_2") (pintype "passive"))
      (node (ref "C66_CNF") (pin "2") (pinfunction "2_2") (pintype "passive"))
      (node (ref "U1") (pin "H19") (pinfunction "VCCINT_H19") (pintype "power_in"))
      (node (ref "U1") (pin "H8") (pinfunction "VCCINT_H8") (pintype "power_in"))
      (node (ref "U1") (pin "J10") (pinfunction "VCCINT_J10") (pintype "power_in"))
      (node (ref "U1") (pin "J17") (pinfunction "VCCINT_J17") (pintype "power_in"))
      (node (ref "U1") (pin "J18") (pinfunction "VCCINT_J18") (pintype "power_in"))
      (node (ref "U1") (pin "J9") (pinfunction "VCCINT_J9") (pintype "power_in"))
      (node (ref "U1") (pin "K10") (pinfunction "VCCINT_K10") (pintype "power_in"))
      (node (ref "U1") (pin "K17") (pinfunction "VCCINT_K17") (pintype "power_in"))
      (node (ref "U1") (pin "K18") (pinfunction "VCCINT_K18") (pintype "power_in"))
      (node (ref "U1") (pin "K9") (pinfunction "VCCINT_K9") (pintype "power_in"))
      (node (ref "U1") (pin "U10") (pinfunction "VCCINT_U10") (pintype "power_in"))
      (node (ref "U1") (pin "U17") (pinfunction "VCCINT_U17") (pintype "power_in"))
      (node (ref "U1") (pin "U18") (pinfunction "VCCINT_U18") (pintype "power_in"))
      (node (ref "U1") (pin "U9") (pinfunction "VCCINT_U9") (pintype "power_in"))
      (node (ref "U1") (pin "V10") (pinfunction "VCCINT_V10") (pintype "power_in"))
      (node (ref "U1") (pin "V17") (pinfunction "VCCINT_V17") (pintype "power_in"))
      (node (ref "U1") (pin "V18") (pinfunction "VCCINT_V18") (pintype "power_in"))
      (node (ref "U1") (pin "V9") (pinfunction "VCCINT_V9") (pintype "power_in"))
      (node (ref "U1") (pin "W19") (pinfunction "VCCINT_W19") (pintype "power_in"))
      (node (ref "U1") (pin "W8") (pinfunction "VCCINT_W8") (pintype "power_in"))
    )
    (net (code "9") (name "2.5V") (class "Default")
      (node (ref "C67_CNF") (pin "2") (pinfunction "2_2") (pintype "passive"))
      (node (ref "C68_CNF") (pin "2") (pinfunction "2_2") (pintype "passive"))
      (node (ref "C69_CNF") (pin "2") (pinfunction "2_2") (pintype "passive"))
      (node (ref "C70_CNF") (pin "2") (pinfunction "2_2") (pintype "passive"))
      (node (ref "C71_CNF") (pin "2") (pinfunction "2_2") (pintype "passive"))
      (node (ref "C72_CNF") (pin "2") (pinfunction "2_2") (pintype "passive"))
      (node (ref "C73_CNF") (pin "2") (pinfunction "2_2") (pintype "passive"))
      (node (ref "C74_CNF") (pin "2") (pinfunction "2_2") (pintype "passive"))
      (node (ref "C75_CNF") (pin "2") (pinfunction "2_2") (pintype "passive"))
      (node (ref "C76_CNF") (pin "2") (pinfunction "2_2") (pintype "passive"))
      (node (ref "C77_CNF") (pin "2") (pinfunction "2_2") (pintype "passive"))
      (node (ref "C78_CNF") (pin "2") (pinfunction "2_2") (pintype "passive"))
      (node (ref "C79_CNF") (pin "2") (pinfunction "2_2") (pintype "passive"))
      (node (ref "C80_CNF") (pin "2") (pinfunction "2_2") (pintype "passive"))
      (node (ref "C81_CNF") (pin "2") (pinfunction "2_2") (pintype "passive"))
      (node (ref "C82_CNF") (pin "2") (pinfunction "2_2") (pintype "passive"))
      (node (ref "C83_CNF") (pin "2") (pinfunction "2_2") (pintype "passive"))
      (node (ref "C84_CNF") (pin "2") (pinfunction "2_2") (pintype "passive"))
      (node (ref "C85_CNF") (pin "2") (pinfunction "2_2") (pintype "passive"))
      (node (ref "C86_CNF") (pin "2") (pinfunction "2_2") (pintype "passive"))
      (node (ref "C87_CNF") (pin "2") (pinfunction "2_2") (pintype "passive"))
      (node (ref "C88_CNF") (pin "2") (pinfunction "2_2") (pintype "passive"))
      (node (ref "C89_CNF") (pin "2") (pinfunction "2_2") (pintype "passive"))
      (node (ref "C90_CNF") (pin "2") (pinfunction "2_2") (pintype "passive"))
      (node (ref "C91_CNF") (pin "2") (pinfunction "2_2") (pintype "passive"))
      (node (ref "C92_CNF") (pin "2") (pinfunction "2_2") (pintype "passive"))
      (node (ref "C93_CNF") (pin "2") (pinfunction "2_2") (pintype "passive"))
      (node (ref "C94_CNF") (pin "2") (pinfunction "2_2") (pintype "passive"))
      (node (ref "C95_CNF") (pin "2") (pinfunction "2_2") (pintype "passive"))
      (node (ref "C96_CNF") (pin "2") (pinfunction "2_2") (pintype "passive"))
      (node (ref "C97_CNF") (pin "2") (pinfunction "2_2") (pintype "passive"))
      (node (ref "C98_CNF") (pin "2") (pinfunction "2_2") (pintype "passive"))
      (node (ref "R1_CNF") (pin "1") (pinfunction "1_1") (pintype "passive"))
      (node (ref "R2_CNF") (pin "1") (pinfunction "1_1") (pintype "passive"))
      (node (ref "U1") (pin "A18") (pinfunction "VCCAUX_A18") (pintype "power_in"))
      (node (ref "U1") (pin "A2") (pinfunction "VCCAUX_A2") (pintype "power_in"))
      (node (ref "U1") (pin "A25") (pinfunction "VCCAUX_A25") (pintype "power_in"))
      (node (ref "U1") (pin "A9") (pinfunction "VCCAUX_A9") (pintype "power_in"))
      (node (ref "U1") (pin "AC3") (pinfunction "M1_AC3") (pintype "input"))
      (node (ref "U1") (pin "AE1") (pinfunction "VCCAUX_AE1") (pintype "power_in"))
      (node (ref "U1") (pin "AE26") (pinfunction "VCCAUX_AE26") (pintype "power_in"))
      (node (ref "U1") (pin "AF18") (pinfunction "VCCAUX_AF18") (pintype "power_in"))
      (node (ref "U1") (pin "AF2") (pinfunction "VCCAUX_AF2") (pintype "power_in"))
      (node (ref "U1") (pin "AF25") (pinfunction "VCCAUX_AF25") (pintype "power_in"))
      (node (ref "U1") (pin "AF3") (pinfunction "M2_AF3") (pintype "input"))
      (node (ref "U1") (pin "AF9") (pinfunction "VCCAUX_AF9") (pintype "power_in"))
      (node (ref "U1") (pin "B1") (pinfunction "VCCAUX_B1") (pintype "power_in"))
      (node (ref "U1") (pin "B26") (pinfunction "VCCAUX_B26") (pintype "power_in"))
      (node (ref "U1") (pin "C2") (pinfunction "HSWAP_EN_C2") (pintype "input"))
      (node (ref "U1") (pin "G3") (pinfunction "VCCO_7_G3") (pintype "power_in"))
      (node (ref "U1") (pin "J1") (pinfunction "VCCAUX_J1") (pintype "power_in"))
      (node (ref "U1") (pin "J26") (pinfunction "VCCAUX_J26") (pintype "power_in"))
      (node (ref "U1") (pin "J8") (pinfunction "VCCO_7_J8") (pintype "power_in"))
      (node (ref "U1") (pin "K8") (pinfunction "VCCO_7_K8") (pintype "power_in"))
      (node (ref "U1") (pin "L3") (pinfunction "VCCO_7_L3") (pintype "power_in"))
      (node (ref "U1") (pin "L9") (pinfunction "VCCO_7_L9") (pintype "power_in"))
      (node (ref "U1") (pin "M9") (pinfunction "VCCO_7_M9") (pintype "power_in"))
      (node (ref "U1") (pin "N10") (pinfunction "VCCO_7_N10") (pintype "power_in"))
      (node (ref "U1") (pin "N9") (pinfunction "VCCO_7_N9") (pintype "power_in"))
      (node (ref "U1") (pin "P10") (pinfunction "VCCO_6_P10") (pintype "power_in"))
      (node (ref "U1") (pin "P9") (pinfunction "VCCO_6_P9") (pintype "power_in"))
      (node (ref "U1") (pin "R9") (pinfunction "VCCO_6_R9") (pintype "power_in"))
      (node (ref "U1") (pin "T3") (pinfunction "VCCO_6_T3") (pintype "power_in"))
      (node (ref "U1") (pin "T9") (pinfunction "VCCO_6_T9") (pintype "power_in"))
      (node (ref "U1") (pin "U8") (pinfunction "VCCO_6_U8") (pintype "power_in"))
      (node (ref "U1") (pin "V1") (pinfunction "VCCAUX_V1") (pintype "power_in"))
      (node (ref "U1") (pin "V26") (pinfunction "VCCAUX_V26") (pintype "power_in"))
      (node (ref "U1") (pin "V8") (pinfunction "VCCO_6_V8") (pintype "power_in"))
      (node (ref "U1") (pin "Y3") (pinfunction "VCCO_6_Y3") (pintype "power_in"))
    )
    (net (code "10") (name "3.3V") (class "Default")
      (node (ref "C10_CNF") (pin "2") (pinfunction "2_2") (pintype "passive"))
      (node (ref "C11_CNF") (pin "2") (pinfunction "2_2") (pintype "passive"))
      (node (ref "C12_CNF") (pin "2") (pinfunction "2_2") (pintype "passive"))
      (node (ref "C13_CNF") (pin "2") (pinfunction "2_2") (pintype "passive"))
      (node (ref "C14_CNF") (pin "2") (pinfunction "2_2") (pintype "passive"))
      (node (ref "C15_CNF") (pin "2") (pinfunction "2_2") (pintype "passive"))
      (node (ref "C16_CNF") (pin "2") (pinfunction "2_2") (pintype "passive"))
      (node (ref "C17_CNF") (pin "2") (pinfunction "2_2") (pintype "passive"))
      (node (ref "C18_CNF") (pin "2") (pinfunction "2_2") (pintype "passive"))
      (node (ref "C19_CNF") (pin "2") (pinfunction "2_2") (pintype "passive"))
      (node (ref "C1_CNF") (pin "1") (pinfunction "1_1") (pintype "passive"))
      (node (ref "C20_CNF") (pin "2") (pinfunction "2_2") (pintype "passive"))
      (node (ref "C21_CNF") (pin "2") (pinfunction "2_2") (pintype "passive"))
      (node (ref "C22_CNF") (pin "2") (pinfunction "2_2") (pintype "passive"))
      (node (ref "C23_CNF") (pin "2") (pinfunction "2_2") (pintype "passive"))
      (node (ref "C24_CNF") (pin "2") (pinfunction "2_2") (pintype "passive"))
      (node (ref "C25_CNF") (pin "2") (pinfunction "2_2") (pintype "passive"))
      (node (ref "C26_CNF") (pin "2") (pinfunction "2_2") (pintype "passive"))
      (node (ref "C27_CNF") (pin "2") (pinfunction "2_2") (pintype "passive"))
      (node (ref "C28_CNF") (pin "2") (pinfunction "2_2") (pintype "passive"))
      (node (ref "C29_CNF") (pin "2") (pinfunction "2_2") (pintype "passive"))
      (node (ref "C2_CNF") (pin "1") (pinfunction "1_1") (pintype "passive"))
      (node (ref "C30_CNF") (pin "2") (pinfunction "2_2") (pintype "passive"))
      (node (ref "C31_CNF") (pin "2") (pinfunction "2_2") (pintype "passive"))
      (node (ref "C32_CNF") (pin "2") (pinfunction "2_2") (pintype "passive"))
      (node (ref "C33_CNF") (pin "2") (pinfunction "2_2") (pintype "passive"))
      (node (ref "C34_CNF") (pin "2") (pinfunction "2_2") (pintype "passive"))
      (node (ref "C35_CNF") (pin "2") (pinfunction "2_2") (pintype "passive"))
      (node (ref "C36_CNF") (pin "2") (pinfunction "2_2") (pintype "passive"))
      (node (ref "C37_CNF") (pin "2") (pinfunction "2_2") (pintype "passive"))
      (node (ref "C38_CNF") (pin "2") (pinfunction "2_2") (pintype "passive"))
      (node (ref "C39_CNF") (pin "2") (pinfunction "2_2") (pintype "passive"))
      (node (ref "C3_CNF") (pin "1") (pinfunction "1_1") (pintype "passive"))
      (node (ref "C40_CNF") (pin "2") (pinfunction "2_2") (pintype "passive"))
      (node (ref "C41_CNF") (pin "2") (pinfunction "2_2") (pintype "passive"))
      (node (ref "C42_CNF") (pin "2") (pinfunction "2_2") (pintype "passive"))
      (node (ref "C43_CNF") (pin "2") (pinfunction "2_2") (pintype "passive"))
      (node (ref "C44_CNF") (pin "2") (pinfunction "2_2") (pintype "passive"))
      (node (ref "C4_CNF") (pin "1") (pinfunction "1_1") (pintype "passive"))
      (node (ref "C5_CNF") (pin "1") (pinfunction "1_1") (pintype "passive"))
      (node (ref "C6_CNF") (pin "1") (pinfunction "1_1") (pintype "passive"))
      (node (ref "C7_CNF") (pin "2") (pinfunction "2_2") (pintype "passive"))
      (node (ref "C8_CNF") (pin "2") (pinfunction "2_2") (pintype "passive"))
      (node (ref "C9_CNF") (pin "2") (pinfunction "2_2") (pintype "passive"))
      (node (ref "U1") (pin "AD11") (pinfunction "VCCO_5_AD11") (pintype "power_in"))
      (node (ref "U1") (pin "AD16") (pinfunction "VCCO_4_AD16") (pintype "power_in"))
      (node (ref "U1") (pin "AD20") (pinfunction "VCCO_4_AD20") (pintype "power_in"))
      (node (ref "U1") (pin "AD7") (pinfunction "VCCO_5_AD7") (pintype "power_in"))
      (node (ref "U1") (pin "C11") (pinfunction "VCCO_0_C11") (pintype "power_in"))
      (node (ref "U1") (pin "C16") (pinfunction "VCCO_1_C16") (pintype "power_in"))
      (node (ref "U1") (pin "C20") (pinfunction "VCCO_1_C20") (pintype "power_in"))
      (node (ref "U1") (pin "C7") (pinfunction "VCCO_0_C7") (pintype "power_in"))
      (node (ref "U1") (pin "G24") (pinfunction "VCCO_2_G24") (pintype "power_in"))
      (node (ref "U1") (pin "H10") (pinfunction "VCCO_0_H10") (pintype "power_in"))
      (node (ref "U1") (pin "H17") (pinfunction "VCCO_1_H17") (pintype "power_in"))
      (node (ref "U1") (pin "H18") (pinfunction "VCCO_1_H18") (pintype "power_in"))
      (node (ref "U1") (pin "H9") (pinfunction "VCCO_0_H9") (pintype "power_in"))
      (node (ref "U1") (pin "J11") (pinfunction "VCCO_0_J11") (pintype "power_in"))
      (node (ref "U1") (pin "J12") (pinfunction "VCCO_0_J12") (pintype "power_in"))
      (node (ref "U1") (pin "J13") (pinfunction "VCCO_0_J13") (pintype "power_in"))
      (node (ref "U1") (pin "J14") (pinfunction "VCCO_1_J14") (pintype "power_in"))
      (node (ref "U1") (pin "J15") (pinfunction "VCCO_1_J15") (pintype "power_in"))
      (node (ref "U1") (pin "J16") (pinfunction "VCCO_1_J16") (pintype "power_in"))
      (node (ref "U1") (pin "J19") (pinfunction "VCCO_2_J19") (pintype "power_in"))
      (node (ref "U1") (pin "K13") (pinfunction "VCCO_0_K13") (pintype "power_in"))
      (node (ref "U1") (pin "K14") (pinfunction "VCCO_1_K14") (pintype "power_in"))
      (node (ref "U1") (pin "K19") (pinfunction "VCCO_2_K19") (pintype "power_in"))
      (node (ref "U1") (pin "L18") (pinfunction "VCCO_2_L18") (pintype "power_in"))
      (node (ref "U1") (pin "L24") (pinfunction "VCCO_2_L24") (pintype "power_in"))
      (node (ref "U1") (pin "M18") (pinfunction "VCCO_2_M18") (pintype "power_in"))
      (node (ref "U1") (pin "N17") (pinfunction "VCCO_2_N17") (pintype "power_in"))
      (node (ref "U1") (pin "N18") (pinfunction "VCCO_2_N18") (pintype "power_in"))
      (node (ref "U1") (pin "P17") (pinfunction "VCCO_3_P17") (pintype "power_in"))
      (node (ref "U1") (pin "P18") (pinfunction "VCCO_3_P18") (pintype "power_in"))
      (node (ref "U1") (pin "R18") (pinfunction "VCCO_3_R18") (pintype "power_in"))
      (node (ref "U1") (pin "T18") (pinfunction "VCCO_3_T18") (pintype "power_in"))
      (node (ref "U1") (pin "T24") (pinfunction "VCCO_3_T24") (pintype "power_in"))
      (node (ref "U1") (pin "U13") (pinfunction "VCCO_5_U13") (pintype "power_in"))
      (node (ref "U1") (pin "U14") (pinfunction "VCCO_4_U14") (pintype "power_in"))
      (node (ref "U1") (pin "U19") (pinfunction "VCCO_3_U19") (pintype "power_in"))
      (node (ref "U1") (pin "V11") (pinfunction "VCCO_5_V11") (pintype "power_in"))
      (node (ref "U1") (pin "V12") (pinfunction "VCCO_5_V12") (pintype "power_in"))
      (node (ref "U1") (pin "V13") (pinfunction "VCCO_5_V13") (pintype "power_in"))
      (node (ref "U1") (pin "V14") (pinfunction "VCCO_4_V14") (pintype "power_in"))
      (node (ref "U1") (pin "V15") (pinfunction "VCCO_4_V15") (pintype "power_in"))
      (node (ref "U1") (pin "V16") (pinfunction "VCCO_4_V16") (pintype "power_in"))
      (node (ref "U1") (pin "V19") (pinfunction "VCCO_3_V19") (pintype "power_in"))
      (node (ref "U1") (pin "W10") (pinfunction "VCCO_5_W10") (pintype "power_in"))
      (node (ref "U1") (pin "W17") (pinfunction "VCCO_4_W17") (pintype "power_in"))
      (node (ref "U1") (pin "W18") (pinfunction "VCCO_4_W18") (pintype "power_in"))
      (node (ref "U1") (pin "W9") (pinfunction "VCCO_5_W9") (pintype "power_in"))
      (node (ref "U1") (pin "Y24") (pinfunction "VCCO_3_Y24") (pintype "power_in"))
    )
    (net (code "11") (name "GND") (class "Default")
      (node (ref "C10_CNF") (pin "1") (pinfunction "1_1") (pintype "passive"))
      (node (ref "C11_CNF") (pin "1") (pinfunction "1_1") (pintype "passive"))
      (node (ref "C12_CNF") (pin "1") (pinfunction "1_1") (pintype "passive"))
      (node (ref "C13_CNF") (pin "1") (pinfunction "1_1") (pintype "passive"))
      (node (ref "C14_CNF") (pin "1") (pinfunction "1_1") (pintype "passive"))
      (node (ref "C15_CNF") (pin "1") (pinfunction "1_1") (pintype "passive"))
      (node (ref "C16_CNF") (pin "1") (pinfunction "1_1") (pintype "passive"))
      (node (ref "C17_CNF") (pin "1") (pinfunction "1_1") (pintype "passive"))
      (node (ref "C18_CNF") (pin "1") (pinfunction "1_1") (pintype "passive"))
      (node (ref "C19_CNF") (pin "1") (pinfunction "1_1") (pintype "passive"))
      (node (ref "C1_CNF") (pin "2") (pinfunction "2_2") (pintype "passive"))
      (node (ref "C20_CNF") (pin "1") (pinfunction "1_1") (pintype "passive"))
      (node (ref "C21_CNF") (pin "1") (pinfunction "1_1") (pintype "passive"))
      (node (ref "C22_CNF") (pin "1") (pinfunction "1_1") (pintype "passive"))
      (node (ref "C23_CNF") (pin "1") (pinfunction "1_1") (pintype "passive"))
      (node (ref "C24_CNF") (pin "1") (pinfunction "1_1") (pintype "passive"))
      (node (ref "C25_CNF") (pin "1") (pinfunction "1_1") (pintype "passive"))
      (node (ref "C26_CNF") (pin "1") (pinfunction "1_1") (pintype "passive"))
      (node (ref "C27_CNF") (pin "1") (pinfunction "1_1") (pintype "passive"))
      (node (ref "C28_CNF") (pin "1") (pinfunction "1_1") (pintype "passive"))
      (node (ref "C29_CNF") (pin "1") (pinfunction "1_1") (pintype "passive"))
      (node (ref "C2_CNF") (pin "2") (pinfunction "2_2") (pintype "passive"))
      (node (ref "C30_CNF") (pin "1") (pinfunction "1_1") (pintype "passive"))
      (node (ref "C31_CNF") (pin "1") (pinfunction "1_1") (pintype "passive"))
      (node (ref "C32_CNF") (pin "1") (pinfunction "1_1") (pintype "passive"))
      (node (ref "C33_CNF") (pin "1") (pinfunction "1_1") (pintype "passive"))
      (node (ref "C34_CNF") (pin "1") (pinfunction "1_1") (pintype "passive"))
      (node (ref "C35_CNF") (pin "1") (pinfunction "1_1") (pintype "passive"))
      (node (ref "C36_CNF") (pin "1") (pinfunction "1_1") (pintype "passive"))
      (node (ref "C37_CNF") (pin "1") (pinfunction "1_1") (pintype "passive"))
      (node (ref "C38_CNF") (pin "1") (pinfunction "1_1") (pintype "passive"))
      (node (ref "C39_CNF") (pin "1") (pinfunction "1_1") (pintype "passive"))
      (node (ref "C3_CNF") (pin "2") (pinfunction "2_2") (pintype "passive"))
      (node (ref "C40_CNF") (pin "1") (pinfunction "1_1") (pintype "passive"))
      (node (ref "C41_CNF") (pin "1") (pinfunction "1_1") (pintype "passive"))
      (node (ref "C42_CNF") (pin "1") (pinfunction "1_1") (pintype "passive"))
      (node (ref "C43_CNF") (pin "1") (pinfunction "1_1") (pintype "passive"))
      (node (ref "C44_CNF") (pin "1") (pinfunction "1_1") (pintype "passive"))
      (node (ref "C45_CNF") (pin "1") (pinfunction "1_1") (pintype "passive"))
      (node (ref "C46_CNF") (pin "1") (pinfunction "1_1") (pintype "passive"))
      (node (ref "C47_CNF") (pin "1") (pinfunction "1_1") (pintype "passive"))
      (node (ref "C48_CNF") (pin "1") (pinfunction "1_1") (pintype "passive"))
      (node (ref "C49_CNF") (pin "1") (pinfunction "1_1") (pintype "passive"))
      (node (ref "C4_CNF") (pin "2") (pinfunction "2_2") (pintype "passive"))
      (node (ref "C50_CNF") (pin "1") (pinfunction "1_1") (pintype "passive"))
      (node (ref "C51_CNF") (pin "1") (pinfunction "1_1") (pintype "passive"))
      (node (ref "C52_CNF") (pin "1") (pinfunction "1_1") (pintype "passive"))
      (node (ref "C53_CNF") (pin "1") (pinfunction "1_1") (pintype "passive"))
      (node (ref "C54_CNF") (pin "1") (pinfunction "1_1") (pintype "passive"))
      (node (ref "C55_CNF") (pin "1") (pinfunction "1_1") (pintype "passive"))
      (node (ref "C56_CNF") (pin "1") (pinfunction "1_1") (pintype "passive"))
      (node (ref "C57_CNF") (pin "1") (pinfunction "1_1") (pintype "passive"))
      (node (ref "C58_CNF") (pin "1") (pinfunction "1_1") (pintype "passive"))
      (node (ref "C59_CNF") (pin "1") (pinfunction "1_1") (pintype "passive"))
      (node (ref "C5_CNF") (pin "2") (pinfunction "2_2") (pintype "passive"))
      (node (ref "C60_CNF") (pin "1") (pinfunction "1_1") (pintype "passive"))
      (node (ref "C61_CNF") (pin "1") (pinfunction "1_1") (pintype "passive"))
      (node (ref "C62_CNF") (pin "1") (pinfunction "1_1") (pintype "passive"))
      (node (ref "C63_CNF") (pin "1") (pinfunction "1_1") (pintype "passive"))
      (node (ref "C64_CNF") (pin "1") (pinfunction "1_1") (pintype "passive"))
      (node (ref "C65_CNF") (pin "1") (pinfunction "1_1") (pintype "passive"))
      (node (ref "C66_CNF") (pin "1") (pinfunction "1_1") (pintype "passive"))
      (node (ref "C67_CNF") (pin "1") (pinfunction "1_1") (pintype "passive"))
      (node (ref "C68_CNF") (pin "1") (pinfunction "1_1") (pintype "passive"))
      (node (ref "C69_CNF") (pin "1") (pinfunction "1_1") (pintype "passive"))
      (node (ref "C6_CNF") (pin "2") (pinfunction "2_2") (pintype "passive"))
      (node (ref "C70_CNF") (pin "1") (pinfunction "1_1") (pintype "passive"))
      (node (ref "C71_CNF") (pin "1") (pinfunction "1_1") (pintype "passive"))
      (node (ref "C72_CNF") (pin "1") (pinfunction "1_1") (pintype "passive"))
      (node (ref "C73_CNF") (pin "1") (pinfunction "1_1") (pintype "passive"))
      (node (ref "C74_CNF") (pin "1") (pinfunction "1_1") (pintype "passive"))
      (node (ref "C75_CNF") (pin "1") (pinfunction "1_1") (pintype "passive"))
      (node (ref "C76_CNF") (pin "1") (pinfunction "1_1") (pintype "passive"))
      (node (ref "C77_CNF") (pin "1") (pinfunction "1_1") (pintype "passive"))
      (node (ref "C78_CNF") (pin "1") (pinfunction "1_1") (pintype "passive"))
      (node (ref "C79_CNF") (pin "1") (pinfunction "1_1") (pintype "passive"))
      (node (ref "C7_CNF") (pin "1") (pinfunction "1_1") (pintype "passive"))
      (node (ref "C80_CNF") (pin "1") (pinfunction "1_1") (pintype "passive"))
      (node (ref "C81_CNF") (pin "1") (pinfunction "1_1") (pintype "passive"))
      (node (ref "C82_CNF") (pin "1") (pinfunction "1_1") (pintype "passive"))
      (node (ref "C83_CNF") (pin "1") (pinfunction "1_1") (pintype "passive"))
      (node (ref "C84_CNF") (pin "1") (pinfunction "1_1") (pintype "passive"))
      (node (ref "C85_CNF") (pin "1") (pinfunction "1_1") (pintype "passive"))
      (node (ref "C86_CNF") (pin "1") (pinfunction "1_1") (pintype "passive"))
      (node (ref "C87_CNF") (pin "1") (pinfunction "1_1") (pintype "passive"))
      (node (ref "C88_CNF") (pin "1") (pinfunction "1_1") (pintype "passive"))
      (node (ref "C89_CNF") (pin "1") (pinfunction "1_1") (pintype "passive"))
      (node (ref "C8_CNF") (pin "1") (pinfunction "1_1") (pintype "passive"))
      (node (ref "C90_CNF") (pin "1") (pinfunction "1_1") (pintype "passive"))
      (node (ref "C91_CNF") (pin "1") (pinfunction "1_1") (pintype "passive"))
      (node (ref "C92_CNF") (pin "1") (pinfunction "1_1") (pintype "passive"))
      (node (ref "C93_CNF") (pin "1") (pinfunction "1_1") (pintype "passive"))
      (node (ref "C94_CNF") (pin "1") (pinfunction "1_1") (pintype "passive"))
      (node (ref "C95_CNF") (pin "1") (pinfunction "1_1") (pintype "passive"))
      (node (ref "C96_CNF") (pin "1") (pinfunction "1_1") (pintype "passive"))
      (node (ref "C97_CNF") (pin "1") (pinfunction "1_1") (pintype "passive"))
      (node (ref "C98_CNF") (pin "1") (pinfunction "1_1") (pintype "passive"))
      (node (ref "C9_CNF") (pin "1") (pinfunction "1_1") (pintype "passive"))
      (node (ref "R1_CNF") (pin "2") (pinfunction "2_2") (pintype "passive"))
      (node (ref "U1") (pin "A1") (pinfunction "GND_A1") (pintype "power_in"))
      (node (ref "U1") (pin "A26") (pinfunction "GND_A26") (pintype "power_in"))
      (node (ref "U1") (pin "AC12") (pinfunction "GND_AC12") (pintype "power_in"))
      (node (ref "U1") (pin "AC15") (pinfunction "GND_AC15") (pintype "power_in"))
      (node (ref "U1") (pin "AC23") (pinfunction "GND_AC23") (pintype "power_in"))
      (node (ref "U1") (pin "AC4") (pinfunction "GND_AC4") (pintype "power_in"))
      (node (ref "U1") (pin "AD24") (pinfunction "GND_AD24") (pintype "power_in"))
      (node (ref "U1") (pin "AD3") (pinfunction "GND_AD3") (pintype "power_in"))
      (node (ref "U1") (pin "AE2") (pinfunction "GND_AE2") (pintype "power_in"))
      (node (ref "U1") (pin "AE25") (pinfunction "GND_AE25") (pintype "power_in"))
      (node (ref "U1") (pin "AE3") (pinfunction "M0_AE3") (pintype "input"))
      (node (ref "U1") (pin "AF1") (pinfunction "GND_AF1") (pintype "power_in"))
      (node (ref "U1") (pin "AF26") (pinfunction "GND_AF26") (pintype "power_in"))
      (node (ref "U1") (pin "B2") (pinfunction "GND_B2") (pintype "power_in"))
      (node (ref "U1") (pin "B25") (pinfunction "GND_B25") (pintype "power_in"))
      (node (ref "U1") (pin "C24") (pinfunction "GND_C24") (pintype "power_in"))
      (node (ref "U1") (pin "C3") (pinfunction "GND_C3") (pintype "power_in"))
      (node (ref "U1") (pin "D12") (pinfunction "GND_D12") (pintype "power_in"))
      (node (ref "U1") (pin "D15") (pinfunction "GND_D15") (pintype "power_in"))
      (node (ref "U1") (pin "D23") (pinfunction "GND_D23") (pintype "power_in"))
      (node (ref "U1") (pin "D4") (pinfunction "GND_D4") (pintype "power_in"))
      (node (ref "U1") (pin "K11") (pinfunction "GND_K11") (pintype "power_in"))
      (node (ref "U1") (pin "K12") (pinfunction "GND_K12") (pintype "power_in"))
      (node (ref "U1") (pin "K15") (pinfunction "GND_K15") (pintype "power_in"))
      (node (ref "U1") (pin "K16") (pinfunction "GND_K16") (pintype "power_in"))
      (node (ref "U1") (pin "L10") (pinfunction "GND_L10") (pintype "power_in"))
      (node (ref "U1") (pin "L11") (pinfunction "GND_L11") (pintype "power_in"))
      (node (ref "U1") (pin "L12") (pinfunction "GND_L12") (pintype "power_in"))
      (node (ref "U1") (pin "L13") (pinfunction "GND_L13") (pintype "power_in"))
      (node (ref "U1") (pin "L14") (pinfunction "GND_L14") (pintype "power_in"))
      (node (ref "U1") (pin "L15") (pinfunction "GND_L15") (pintype "power_in"))
      (node (ref "U1") (pin "L16") (pinfunction "GND_L16") (pintype "power_in"))
      (node (ref "U1") (pin "L17") (pinfunction "GND_L17") (pintype "power_in"))
      (node (ref "U1") (pin "M10") (pinfunction "GND_M10") (pintype "power_in"))
      (node (ref "U1") (pin "M11") (pinfunction "GND_M11") (pintype "power_in"))
      (node (ref "U1") (pin "M12") (pinfunction "GND_M12") (pintype "power_in"))
      (node (ref "U1") (pin "M13") (pinfunction "GND_M13") (pintype "power_in"))
      (node (ref "U1") (pin "M14") (pinfunction "GND_M14") (pintype "power_in"))
      (node (ref "U1") (pin "M15") (pinfunction "GND_M15") (pintype "power_in"))
      (node (ref "U1") (pin "M16") (pinfunction "GND_M16") (pintype "power_in"))
      (node (ref "U1") (pin "M17") (pinfunction "GND_M17") (pintype "power_in"))
      (node (ref "U1") (pin "M23") (pinfunction "GND_M23") (pintype "power_in"))
      (node (ref "U1") (pin "M4") (pinfunction "GND_M4") (pintype "power_in"))
      (node (ref "U1") (pin "N11") (pinfunction "GND_N11") (pintype "power_in"))
      (node (ref "U1") (pin "N12") (pinfunction "GND_N12") (pintype "power_in"))
      (node (ref "U1") (pin "N13") (pinfunction "GND_N13") (pintype "power_in"))
      (node (ref "U1") (pin "N14") (pinfunction "GND_N14") (pintype "power_in"))
      (node (ref "U1") (pin "N15") (pinfunction "GND_N15") (pintype "power_in"))
      (node (ref "U1") (pin "N16") (pinfunction "GND_N16") (pintype "power_in"))
      (node (ref "U1") (pin "P11") (pinfunction "GND_P11") (pintype "power_in"))
      (node (ref "U1") (pin "P12") (pinfunction "GND_P12") (pintype "power_in"))
      (node (ref "U1") (pin "P13") (pinfunction "GND_P13") (pintype "power_in"))
      (node (ref "U1") (pin "P14") (pinfunction "GND_P14") (pintype "power_in"))
      (node (ref "U1") (pin "P15") (pinfunction "GND_P15") (pintype "power_in"))
      (node (ref "U1") (pin "P16") (pinfunction "GND_P16") (pintype "power_in"))
      (node (ref "U1") (pin "R10") (pinfunction "GND_R10") (pintype "power_in"))
      (node (ref "U1") (pin "R11") (pinfunction "GND_R11") (pintype "power_in"))
      (node (ref "U1") (pin "R12") (pinfunction "GND_R12") (pintype "power_in"))
      (node (ref "U1") (pin "R13") (pinfunction "GND_R13") (pintype "power_in"))
      (node (ref "U1") (pin "R14") (pinfunction "GND_R14") (pintype "power_in"))
      (node (ref "U1") (pin "R15") (pinfunction "GND_R15") (pintype "power_in"))
      (node (ref "U1") (pin "R16") (pinfunction "GND_R16") (pintype "power_in"))
      (node (ref "U1") (pin "R17") (pinfunction "GND_R17") (pintype "power_in"))
      (node (ref "U1") (pin "R23") (pinfunction "GND_R23") (pintype "power_in"))
      (node (ref "U1") (pin "R4") (pinfunction "GND_R4") (pintype "power_in"))
      (node (ref "U1") (pin "T10") (pinfunction "GND_T10") (pintype "power_in"))
      (node (ref "U1") (pin "T11") (pinfunction "GND_T11") (pintype "power_in"))
      (node (ref "U1") (pin "T12") (pinfunction "GND_T12") (pintype "power_in"))
      (node (ref "U1") (pin "T13") (pinfunction "GND_T13") (pintype "power_in"))
      (node (ref "U1") (pin "T14") (pinfunction "GND_T14") (pintype "power_in"))
      (node (ref "U1") (pin "T15") (pinfunction "GND_T15") (pintype "power_in"))
      (node (ref "U1") (pin "T16") (pinfunction "GND_T16") (pintype "power_in"))
      (node (ref "U1") (pin "T17") (pinfunction "GND_T17") (pintype "power_in"))
      (node (ref "U1") (pin "U11") (pinfunction "GND_U11") (pintype "power_in"))
      (node (ref "U1") (pin "U12") (pinfunction "GND_U12") (pintype "power_in"))
      (node (ref "U1") (pin "U15") (pinfunction "GND_U15") (pintype "power_in"))
      (node (ref "U1") (pin "U16") (pinfunction "GND_U16") (pintype "power_in"))
    )
    (net (code "12") (name "Net-(U1C-CCLK)") (class "Default")
      (node (ref "R3_CNF") (pin "2") (pinfunction "2_2") (pintype "passive"))
      (node (ref "U1") (pin "AD26") (pinfunction "CCLK_AD26") (pintype "bidirectional"))
    )
    (net (code "13") (name "Net-(U1C-PROG_B)") (class "Default")
      (node (ref "R4_CNF") (pin "2") (pinfunction "2_2") (pintype "passive"))
      (node (ref "U1") (pin "D3") (pinfunction "PROG_B_D3") (pintype "input"))
    )
  )
)
